# openSX70_ALPHA_V7-20181101.net
KiCad netlist of a schematic drawn in EAGLE
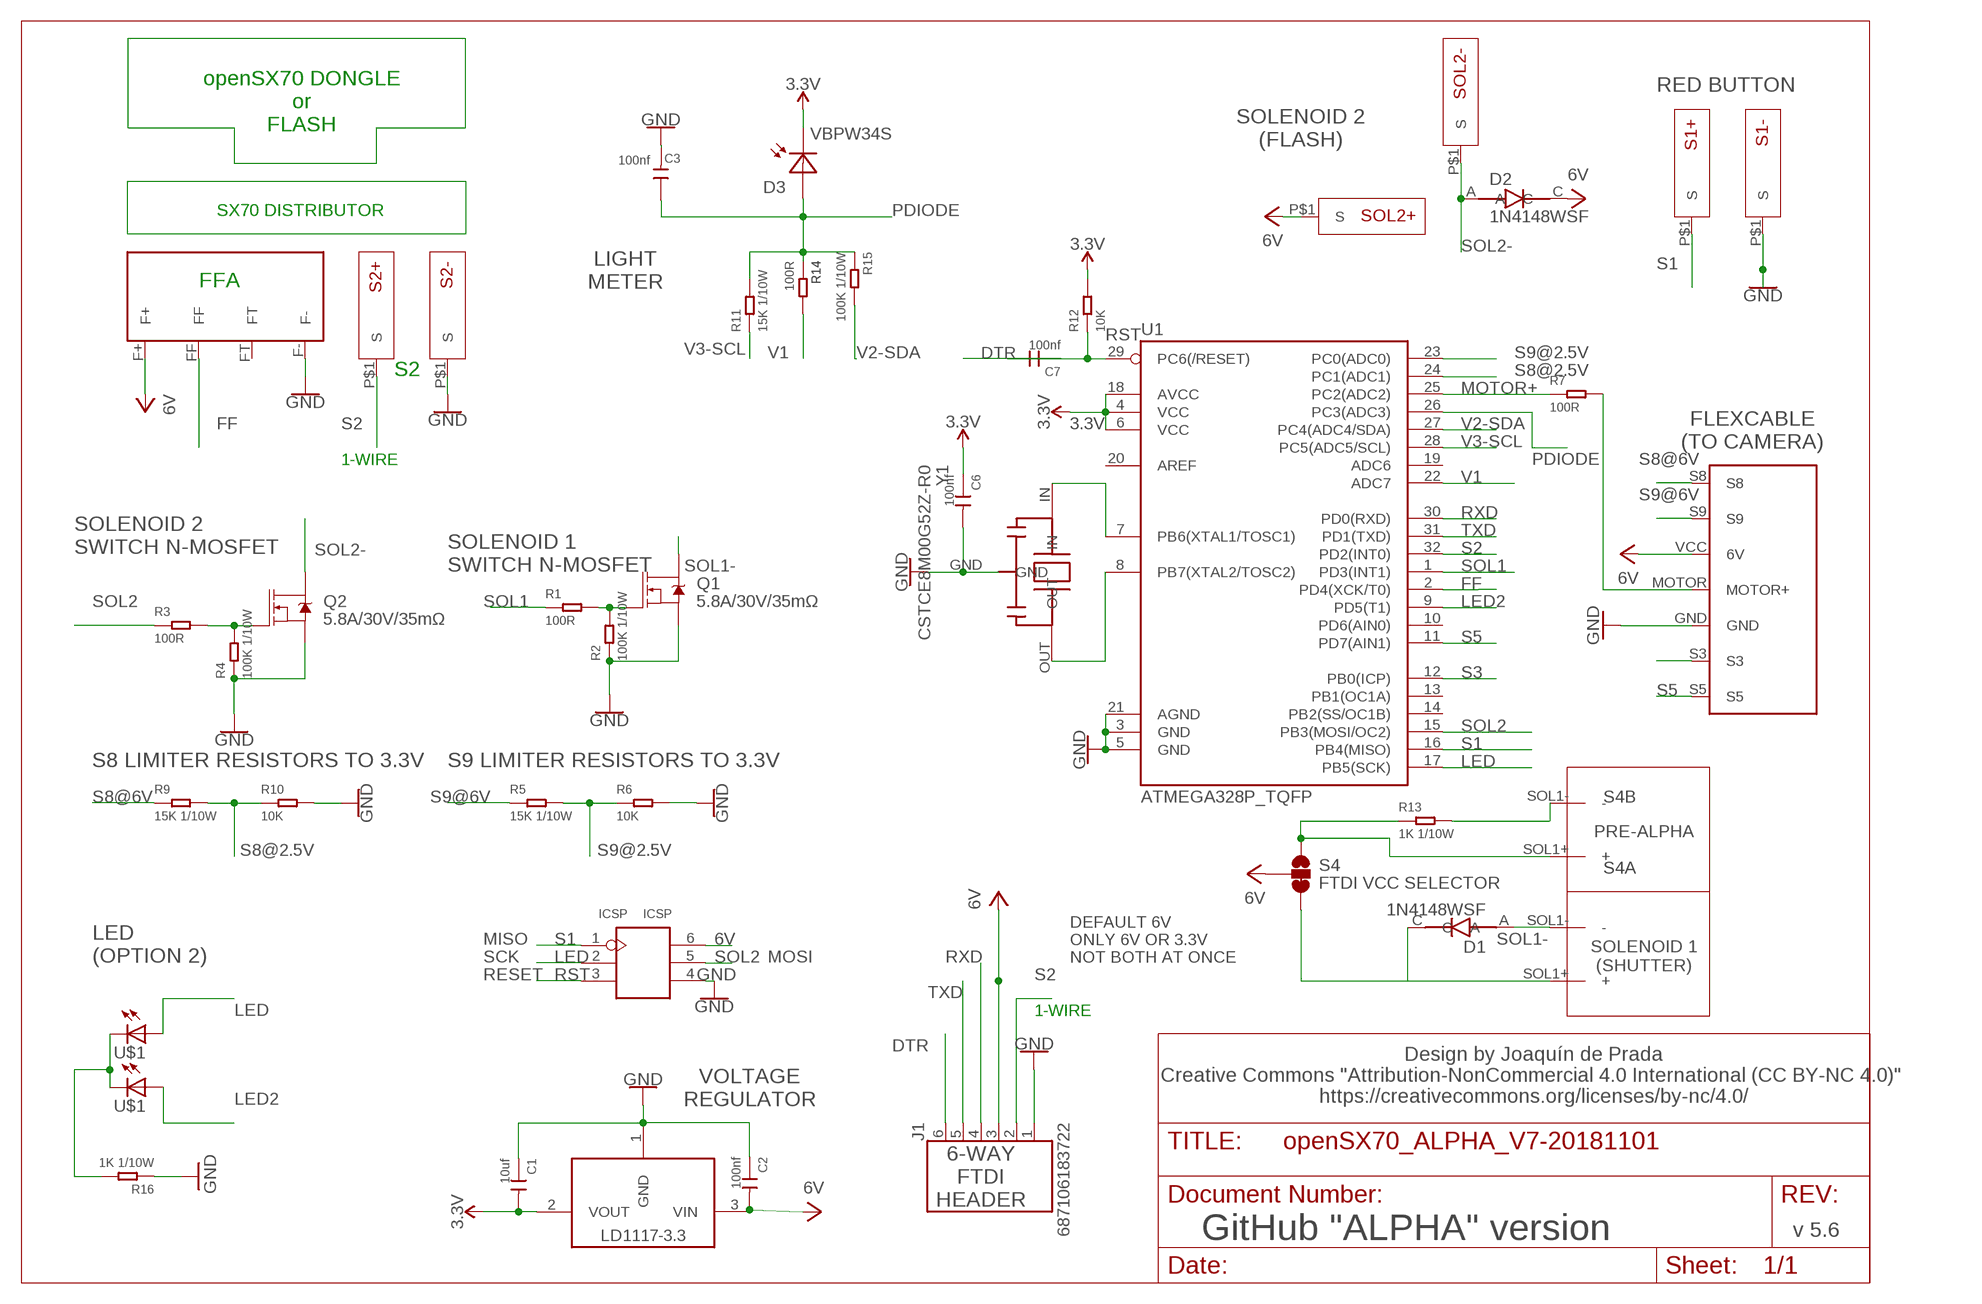
[diagram p0: schematic, sheet 1]

(export (version "E")
  (design (tool "Eeschema 10.0.6"))
  (components
    (comp (ref "C1")
      (value "10uf")
      (footprint "eagle-import:C0603")
      (fields (field (name "MPN") "CC0603KRX5R6BB106"))
      (libsource (lib "eagle-import") (part "CERAMIC-10UF-10V-10%-X5R(0603)"))
    )
    (comp (ref "C2")
      (value "100nf")
      (footprint "eagle-import:C0603")
      (fields (field (name "MPN") "CC0603KRX7R9BB104"))
      (libsource (lib "eagle-import") (part "CERAMIC-100NF-50V-10%-X7R(0603)"))
    )
    (comp (ref "C3")
      (value "100nf")
      (footprint "eagle-import:C0603")
      (fields (field (name "MPN") "CC0603KRX7R9BB104"))
      (libsource (lib "eagle-import") (part "CERAMIC-100NF-50V-10%-X7R(0603)"))
    )
    (comp (ref "C6")
      (value "100nf")
      (footprint "eagle-import:C0603")
      (fields (field (name "MPN") "CC0603KRX7R9BB104"))
      (libsource (lib "eagle-import") (part "CERAMIC-100NF-50V-10%-X7R(0603)"))
    )
    (comp (ref "C7")
      (value "100nf")
      (footprint "eagle-import:C0603")
      (fields (field (name "MPN") "CC0603KRX7R9BB104"))
      (libsource (lib "eagle-import") (part "CERAMIC-100NF-50V-10%-X7R(0603)"))
    )
    (comp (ref "D1")
      (value "1N4148WSF")
      (footprint "eagle-import:SODFL2512X100N")
      (fields (field (name "MANUFACTURER") "Fairchild Semiconductor"))
      (libsource (lib "eagle-import") (part "1N4148WS"))
    )
    (comp (ref "D2")
      (value "1N4148WSF")
      (footprint "eagle-import:SODFL2512X100N")
      (fields (field (name "MANUFACTURER") "Fairchild Semiconductor"))
      (libsource (lib "eagle-import") (part "1N4148WS"))
    )
    (comp (ref "D3")
      (value "VBPW34S")
      (footprint "eagle-import:SOD6439X130N")
      (fields (field (name "DIGI-KEY_PART_NUMBER") "751-1500-1-ND") (field (name "MF") "Vishay"))
      (libsource (lib "eagle-import") (part "VBPW34S"))
    )
    (comp (ref "ICSP")
      (value "ICSP")
      (footprint "eagle-import:H2X3-2.54")
      (libsource (lib "eagle-import") (part "ICSP"))
    )
    (comp (ref "J1")
      (value "687106183722")
      (footprint "eagle-import:687106183722")
      (fields (field (name "MF") "Wurth Electronics"))
      (libsource (lib "eagle-import") (part "687106183722"))
    )
    (comp (ref "LD11172.5V")
      (value "LD1117 2.5V")
      (footprint "eagle-import:SOT223")
      (fields (field (name "MF") "Advanced Monolithic Systems") (field (name "MP") "AMS1117-5.0"))
      (libsource (lib "eagle-import") (part "LD1117-3.3"))
    )
    (comp (ref "Q1")
      (value "5.8A/30V/35mΩ")
      (footprint "eagle-import:SOT23-3")
      (libsource (lib "eagle-import") (part "MOSFET-NCH-AO3404A"))
    )
    (comp (ref "Q2")
      (value "5.8A/30V/35mΩ")
      (footprint "eagle-import:SOT23-3")
      (libsource (lib "eagle-import") (part "MOSFET-NCH-AO3404A"))
    )
    (comp (ref "R1")
      (value "100R")
      (footprint "eagle-import:R0603")
      (fields (field (name "MPN") "RC0603JR-07100RL"))
      (libsource (lib "eagle-import") (part "SMD-RES-100R-5%-1/10W(0603)"))
    )
    (comp (ref "R2")
      (value "100K 1/10W")
      (footprint "eagle-import:R0603")
      (fields (field (name "MPN") "RC0603JR-07100KL"))
      (libsource (lib "eagle-import") (part "SMD-RES-100K-5%-1/10W(0603)"))
    )
    (comp (ref "R3")
      (value "100R")
      (footprint "eagle-import:R0603")
      (fields (field (name "MPN") "RC0603JR-07100RL"))
      (libsource (lib "eagle-import") (part "SMD-RES-100R-5%-1/10W(0603)"))
    )
    (comp (ref "R4")
      (value "100K 1/10W")
      (footprint "eagle-import:R0603")
      (fields (field (name "MPN") "RC0603JR-07100KL"))
      (libsource (lib "eagle-import") (part "SMD-RES-100K-5%-1/10W(0603)"))
    )
    (comp (ref "R5")
      (value "15K 1/10W")
      (footprint "eagle-import:R0603")
      (fields (field (name "MPN") "RC0603FR-0715KL"))
      (libsource (lib "eagle-import") (part "SMD-RES-15K-1%-1/10W(0603)"))
    )
    (comp (ref "R6")
      (value "10K")
      (footprint "eagle-import:R0603")
      (fields (field (name "MPN") "RC0603FR-0710KL"))
      (libsource (lib "eagle-import") (part "SMD-RES-10K-1%-1/10W(0603)"))
    )
    (comp (ref "R7")
      (value "100R")
      (footprint "eagle-import:R0603")
      (fields (field (name "MPN") "RC0603JR-07100RL"))
      (libsource (lib "eagle-import") (part "SMD-RES-100R-5%-1/10W(0603)"))
    )
    (comp (ref "R9")
      (value "15K 1/10W")
      (footprint "eagle-import:R0603")
      (fields (field (name "MPN") "RC0603FR-0715KL"))
      (libsource (lib "eagle-import") (part "SMD-RES-15K-1%-1/10W(0603)"))
    )
    (comp (ref "R10")
      (value "10K")
      (footprint "eagle-import:R0603")
      (fields (field (name "MPN") "RC0603FR-0710KL"))
      (libsource (lib "eagle-import") (part "SMD-RES-10K-1%-1/10W(0603)"))
    )
    (comp (ref "R11")
      (value "15K 1/10W")
      (footprint "eagle-import:R0603")
      (fields (field (name "MPN") "RC0603FR-0715KL"))
      (libsource (lib "eagle-import") (part "SMD-RES-15K-1%-1/10W(0603)"))
    )
    (comp (ref "R12")
      (value "10K")
      (footprint "eagle-import:R0603")
      (fields (field (name "MPN") "RC0603FR-0710KL"))
      (libsource (lib "eagle-import") (part "SMD-RES-10K-1%-1/10W(0603)"))
    )
    (comp (ref "R13")
      (value "1K 1/10W")
      (footprint "eagle-import:R0603")
      (fields (field (name "MPN") "RC0603JR-071KL"))
      (libsource (lib "eagle-import") (part "SMD-RES-1K-5%-1/10W(0603)"))
    )
    (comp (ref "R14")
      (value "100R")
      (footprint "eagle-import:R0603")
      (fields (field (name "MPN") "RC0603JR-07100RL"))
      (libsource (lib "eagle-import") (part "SMD-RES-100R-5%-1/10W(0603)"))
    )
    (comp (ref "R15")
      (value "100K 1/10W")
      (footprint "eagle-import:R0603")
      (fields (field (name "MPN") "RC0603JR-07100KL"))
      (libsource (lib "eagle-import") (part "SMD-RES-100K-5%-1/10W(0603)"))
    )
    (comp (ref "R16")
      (value "1K 1/10W")
      (footprint "eagle-import:R0603")
      (fields (field (name "MPN") "RC0603JR-071KL"))
      (libsource (lib "eagle-import") (part "SMD-RES-1K-5%-1/10W(0603)"))
    )
    (comp (ref "S1+")
      (value "SX70-S-PAD-NEW")
      (footprint "eagle-import:SX70-S-PAD2")
      (libsource (lib "eagle-import") (part "SX70-S-PAD-NEW"))
    )
    (comp (ref "S1-")
      (value "SX70-S-PAD-NEW")
      (footprint "eagle-import:SX70-S-PAD2")
      (libsource (lib "eagle-import") (part "SX70-S-PAD-NEW"))
    )
    (comp (ref "S2+")
      (value "SX70-S-PAD-NEW")
      (footprint "eagle-import:SX70-S-PAD2")
      (libsource (lib "eagle-import") (part "SX70-S-PAD-NEW"))
    )
    (comp (ref "S2-")
      (value "SX70-S-PAD-NEW")
      (footprint "eagle-import:SX70-S-PAD2")
      (libsource (lib "eagle-import") (part "SX70-S-PAD-NEW"))
    )
    (comp (ref "S4")
      (value "FTDI VCC SELECTOR")
      (footprint "eagle-import:SMT-JUMPER_3_1-NC_TRACE_SILK")
      (libsource (lib "eagle-import") (part "JUMPER-SMT_3_1-NC_TRACE_SILK"))
    )
    (comp (ref "SOL1")
      (value "SX70-SOLENOID1-2PADS")
      (footprint "eagle-import:SX70-SOLENOID1-2")
      (libsource (lib "eagle-import") (part "SX70-SOLENOID1-2PADS"))
    )
    (comp (ref "SOL2")
      (value "SX70-SOLENOID1-2PADS")
      (footprint "eagle-import:SX70-SOLENOID1-2")
      (libsource (lib "eagle-import") (part "SX70-SOLENOID1-2PADS"))
    )
    (comp (ref "SOL2+")
      (value "SX70-S-PAD-NEW")
      (footprint "eagle-import:SX70-S-PAD2")
      (libsource (lib "eagle-import") (part "SX70-S-PAD-NEW"))
    )
    (comp (ref "SOL2-")
      (value "SX70-S-PAD-NEW")
      (footprint "eagle-import:SX70-S-PAD2")
      (libsource (lib "eagle-import") (part "SX70-S-PAD-NEW"))
    )
    (comp (ref "U$1")
      (value "DUAL-LED-0603-BIS")
      (footprint "eagle-import:LED_APHB1608SYKSURKC")
      (libsource (lib "eagle-import") (part "DUAL-LED-0603-BIS"))
    )
    (comp (ref "U$2")
      (value "FFA")
      (footprint "eagle-import:FFA-PAD-PACKAGE")
      (libsource (lib "eagle-import") (part "SX70-FFA-PAD"))
    )
    (comp (ref "U$3")
      (value "SX70-7-PAD")
      (footprint "eagle-import:SX70-7-PAD-PROPER")
      (libsource (lib "eagle-import") (part "SX70-7-PAD"))
    )
    (comp (ref "U1")
      (value "ATMEGA328P_TQFP")
      (footprint "eagle-import:TQFP32-08")
      (libsource (lib "eagle-import") (part "ATMEGA328P_TQFP"))
    )
    (comp (ref "Y1")
      (value "CSTCE8M00G52Z-R0")
      (footprint "eagle-import:CFP95P160X100-3N")
      (fields (field (name "MF") "Murata") (field (name "MP") "CSTCE16M0V53-R0"))
      (libsource (lib "eagle-import") (part "CSTCE16M0V53-R0"))
    )
  )
  (nets
    (net (code "1") (name "/DTR") (class "Default")
      (node (ref "C7") (pin "1") (pinfunction "1_1") (pintype "passive"))
      (node (ref "J1") (pin "6") (pinfunction "1_6") (pintype "passive"))
    )
    (net (code "2") (name "/FF") (class "Default")
      (node (ref "U$2") (pin "FF") (pinfunction "FF_FF") (pintype "bidirectional"))
      (node (ref "U1") (pin "2") (pinfunction "PD4(XCK/T0)_2") (pintype "bidirectional"))
    )
    (net (code "3") (name "/LED") (class "Default")
      (node (ref "ICSP") (pin "2") (pinfunction "SCK_2") (pintype "bidirectional"))
      (node (ref "U$1") (pin "1") (pinfunction "A_1") (pintype "passive"))
      (node (ref "U1") (pin "17") (pinfunction "PB5(SCK)_17") (pintype "bidirectional"))
    )
    (net (code "4") (name "/LED2") (class "Default")
      (node (ref "U$1") (pin "3") (pinfunction "A1_3") (pintype "passive"))
      (node (ref "U1") (pin "9") (pinfunction "PD5(T1)_9") (pintype "bidirectional"))
    )
    (net (code "5") (name "/MOTOR+") (class "Default")
      (node (ref "R7") (pin "1") (pinfunction "1_1") (pintype "passive"))
      (node (ref "U1") (pin "25") (pinfunction "PC2(ADC2)_25") (pintype "bidirectional"))
    )
    (net (code "6") (name "/PDIODE") (class "Default")
      (node (ref "C3") (pin "1") (pinfunction "1_1") (pintype "passive"))
      (node (ref "D3") (pin "A") (pinfunction "A_A") (pintype "passive"))
      (node (ref "R11") (pin "2") (pinfunction "2_2") (pintype "passive"))
      (node (ref "R14") (pin "1") (pinfunction "1_1") (pintype "passive"))
      (node (ref "R15") (pin "1") (pinfunction "1_1") (pintype "passive"))
      (node (ref "U1") (pin "26") (pinfunction "PC3(ADC3)_26") (pintype "bidirectional"))
    )
    (net (code "7") (name "/RST") (class "Default")
      (node (ref "C7") (pin "2") (pinfunction "2_2") (pintype "passive"))
      (node (ref "ICSP") (pin "3") (pinfunction "RST_3") (pintype "bidirectional"))
      (node (ref "R12") (pin "1") (pinfunction "1_1") (pintype "passive"))
      (node (ref "U1") (pin "29") (pinfunction "PC6(/RESET)_29") (pintype "bidirectional"))
    )
    (net (code "8") (name "/RXD") (class "Default")
      (node (ref "J1") (pin "4") (pinfunction "3_4") (pintype "passive"))
      (node (ref "U1") (pin "30") (pinfunction "PD0(RXD)_30") (pintype "bidirectional"))
    )
    (net (code "9") (name "/S1") (class "Default")
      (node (ref "ICSP") (pin "1") (pinfunction "MISO_1") (pintype "bidirectional"))
      (node (ref "S1+") (pin "P$1") (pinfunction "S_P$1") (pintype "bidirectional"))
      (node (ref "U1") (pin "16") (pinfunction "PB4(MISO)_16") (pintype "bidirectional"))
    )
    (net (code "10") (name "/S2") (class "Default")
      (node (ref "J1") (pin "2") (pinfunction "5_2") (pintype "passive"))
      (node (ref "S2+") (pin "P$1") (pinfunction "S_P$1") (pintype "bidirectional"))
      (node (ref "U1") (pin "32") (pinfunction "PD2(INT0)_32") (pintype "bidirectional"))
    )
    (net (code "11") (name "/S3") (class "Default")
      (node (ref "U$3") (pin "S3") (pinfunction "S3_S3") (pintype "bidirectional"))
      (node (ref "U1") (pin "12") (pinfunction "PB0(ICP)_12") (pintype "bidirectional"))
    )
    (net (code "12") (name "/S5") (class "Default")
      (node (ref "U$3") (pin "S5") (pinfunction "S5_S5") (pintype "bidirectional"))
      (node (ref "U1") (pin "11") (pinfunction "PD7(AIN1)_11") (pintype "bidirectional"))
    )
    (net (code "13") (name "/S8@2.5V") (class "Default")
      (node (ref "R10") (pin "1") (pinfunction "1_1") (pintype "passive"))
      (node (ref "R9") (pin "2") (pinfunction "2_2") (pintype "passive"))
      (node (ref "U1") (pin "24") (pinfunction "PC1(ADC1)_24") (pintype "bidirectional"))
    )
    (net (code "14") (name "/S8@6V") (class "Default")
      (node (ref "R9") (pin "1") (pinfunction "1_1") (pintype "passive"))
      (node (ref "U$3") (pin "S8") (pinfunction "S8_S8") (pintype "bidirectional"))
    )
    (net (code "15") (name "/S9@2.5V") (class "Default")
      (node (ref "R5") (pin "2") (pinfunction "2_2") (pintype "passive"))
      (node (ref "R6") (pin "1") (pinfunction "1_1") (pintype "passive"))
      (node (ref "U1") (pin "23") (pinfunction "PC0(ADC0)_23") (pintype "bidirectional"))
    )
    (net (code "16") (name "/S9@6V") (class "Default")
      (node (ref "R5") (pin "1") (pinfunction "1_1") (pintype "passive"))
      (node (ref "U$3") (pin "S9") (pinfunction "S9_S9") (pintype "bidirectional"))
    )
    (net (code "17") (name "/SOL1") (class "Default")
      (node (ref "R1") (pin "1") (pinfunction "1_1") (pintype "passive"))
      (node (ref "U1") (pin "1") (pinfunction "PD3(INT1)_1") (pintype "bidirectional"))
    )
    (net (code "18") (name "/SOL1-") (class "Default")
      (node (ref "D1") (pin "A") (pinfunction "A_A") (pintype "passive"))
      (node (ref "Q1") (pin "3") (pinfunction "D_3") (pintype "bidirectional"))
      (node (ref "SOL1") (pin "SOL1-") (pinfunction "-_SOL1-") (pintype "bidirectional"))
    )
    (net (code "19") (name "/SOL2") (class "Default")
      (node (ref "ICSP") (pin "5") (pinfunction "MOSI_5") (pintype "bidirectional"))
      (node (ref "R3") (pin "1") (pinfunction "1_1") (pintype "passive"))
      (node (ref "U1") (pin "15") (pinfunction "PB3(MOSI/OC2)_15") (pintype "bidirectional"))
    )
    (net (code "20") (name "/SOL2-") (class "Default")
      (node (ref "D2") (pin "A") (pinfunction "A_A") (pintype "passive"))
      (node (ref "Q2") (pin "3") (pinfunction "D_3") (pintype "bidirectional"))
      (node (ref "SOL2-") (pin "P$1") (pinfunction "S_P$1") (pintype "bidirectional"))
    )
    (net (code "21") (name "/TXD") (class "Default")
      (node (ref "J1") (pin "5") (pinfunction "2_5") (pintype "passive"))
      (node (ref "U1") (pin "31") (pinfunction "PD1(TXD)_31") (pintype "bidirectional"))
    )
    (net (code "22") (name "/V1") (class "Default")
      (node (ref "R14") (pin "2") (pinfunction "2_2") (pintype "passive"))
      (node (ref "U1") (pin "22") (pinfunction "ADC7_22") (pintype "bidirectional"))
    )
    (net (code "23") (name "/V2-SDA") (class "Default")
      (node (ref "R15") (pin "2") (pinfunction "2_2") (pintype "passive"))
      (node (ref "U1") (pin "27") (pinfunction "PC4(ADC4/SDA)_27") (pintype "bidirectional"))
    )
    (net (code "24") (name "/V3-SCL") (class "Default")
      (node (ref "R11") (pin "1") (pinfunction "1_1") (pintype "passive"))
      (node (ref "U1") (pin "28") (pinfunction "PC5(ADC5/SCL)_28") (pintype "bidirectional"))
    )
    (net (code "25") (name "3.3V") (class "Default")
      (node (ref "C1") (pin "2") (pinfunction "2_2") (pintype "passive"))
      (node (ref "C6") (pin "1") (pinfunction "1_1") (pintype "passive"))
      (node (ref "D3") (pin "C") (pinfunction "C_C") (pintype "passive"))
      (node (ref "LD11172.5V") (pin "2") (pinfunction "VOUT_2") (pintype "bidirectional"))
      (node (ref "R12") (pin "2") (pinfunction "2_2") (pintype "passive"))
      (node (ref "U1") (pin "18") (pinfunction "AVCC_18") (pintype "bidirectional"))
      (node (ref "U1") (pin "4") (pinfunction "VCC_4") (pintype "bidirectional"))
      (node (ref "U1") (pin "6") (pinfunction "VCC_6") (pintype "bidirectional"))
    )
    (net (code "26") (name "6V") (class "Default")
      (node (ref "C2") (pin "2") (pinfunction "2_2") (pintype "passive"))
      (node (ref "D2") (pin "C") (pinfunction "C_C") (pintype "passive"))
      (node (ref "ICSP") (pin "6") (pinfunction "VCC_6") (pintype "bidirectional"))
      (node (ref "J1") (pin "3") (pinfunction "4_3") (pintype "passive"))
      (node (ref "LD11172.5V") (pin "3") (pinfunction "VIN_3") (pintype "bidirectional"))
      (node (ref "S4") (pin "2") (pinfunction "2_2") (pintype "passive"))
      (node (ref "SOL2+") (pin "P$1") (pinfunction "S_P$1") (pintype "bidirectional"))
      (node (ref "U$2") (pin "F+") (pinfunction "F+_F+") (pintype "bidirectional"))
      (node (ref "U$3") (pin "VCC") (pinfunction "6V_VCC") (pintype "bidirectional"))
    )
    (net (code "27") (name "GND") (class "Default")
      (node (ref "C1") (pin "1") (pinfunction "1_1") (pintype "passive"))
      (node (ref "C2") (pin "1") (pinfunction "1_1") (pintype "passive"))
      (node (ref "C3") (pin "2") (pinfunction "2_2") (pintype "passive"))
      (node (ref "C6") (pin "2") (pinfunction "2_2") (pintype "passive"))
      (node (ref "ICSP") (pin "4") (pinfunction "GND_4") (pintype "bidirectional"))
      (node (ref "J1") (pin "1") (pinfunction "6_1") (pintype "passive"))
      (node (ref "LD11172.5V") (pin "1") (pinfunction "GND_1") (pintype "bidirectional"))
      (node (ref "Q1") (pin "2") (pinfunction "S_2") (pintype "bidirectional"))
      (node (ref "Q2") (pin "2") (pinfunction "S_2") (pintype "bidirectional"))
      (node (ref "R10") (pin "2") (pinfunction "2_2") (pintype "passive"))
      (node (ref "R16") (pin "1") (pinfunction "1_1") (pintype "passive"))
      (node (ref "R2") (pin "1") (pinfunction "1_1") (pintype "passive"))
      (node (ref "R4") (pin "1") (pinfunction "1_1") (pintype "passive"))
      (node (ref "R6") (pin "2") (pinfunction "2_2") (pintype "passive"))
      (node (ref "S1-") (pin "P$1") (pinfunction "S_P$1") (pintype "bidirectional"))
      (node (ref "S2-") (pin "P$1") (pinfunction "S_P$1") (pintype "bidirectional"))
      (node (ref "U$2") (pin "F-") (pinfunction "F-_F-") (pintype "bidirectional"))
      (node (ref "U$3") (pin "GND") (pinfunction "GND_GND") (pintype "bidirectional"))
      (node (ref "U1") (pin "21") (pinfunction "AGND_21") (pintype "bidirectional"))
      (node (ref "U1") (pin "3") (pinfunction "GND_3") (pintype "bidirectional"))
      (node (ref "U1") (pin "5") (pinfunction "GND_5") (pintype "bidirectional"))
      (node (ref "Y1") (pin "GND") (pinfunction "GND_GND") (pintype "passive"))
    )
    (net (code "28") (name "Net-(Q1-G)") (class "Default")
      (node (ref "Q1") (pin "1") (pinfunction "G_1") (pintype "bidirectional"))
      (node (ref "R1") (pin "2") (pinfunction "2_2") (pintype "passive"))
      (node (ref "R2") (pin "2") (pinfunction "2_2") (pintype "passive"))
    )
    (net (code "29") (name "Net-(Q2-G)") (class "Default")
      (node (ref "Q2") (pin "1") (pinfunction "G_1") (pintype "bidirectional"))
      (node (ref "R3") (pin "2") (pinfunction "2_2") (pintype "passive"))
      (node (ref "R4") (pin "2") (pinfunction "2_2") (pintype "passive"))
    )
    (net (code "30") (name "Net-(SOL1-+)") (class "Default")
      (node (ref "D1") (pin "C") (pinfunction "C_C") (pintype "passive"))
      (node (ref "S4") (pin "3") (pinfunction "3_3") (pintype "passive"))
      (node (ref "SOL1") (pin "SOL1+") (pinfunction "+_SOL1+") (pintype "bidirectional"))
    )
    (net (code "31") (name "Net-(SOL2-+)") (class "Default")
      (node (ref "R13") (pin "1") (pinfunction "1_1") (pintype "passive"))
      (node (ref "S4") (pin "1") (pinfunction "1_1") (pintype "passive"))
      (node (ref "SOL2") (pin "SOL1+") (pinfunction "+_SOL1+") (pintype "bidirectional"))
    )
    (net (code "32") (name "Net-(SOL2--)") (class "Default")
      (node (ref "R13") (pin "2") (pinfunction "2_2") (pintype "passive"))
      (node (ref "SOL2") (pin "SOL1-") (pinfunction "-_SOL1-") (pintype "bidirectional"))
    )
    (net (code "33") (name "Net-(U$1-C)") (class "Default")
      (node (ref "R16") (pin "2") (pinfunction "2_2") (pintype "passive"))
      (node (ref "U$1") (pin "2") (pinfunction "C_2") (pintype "passive"))
      (node (ref "U$1") (pin "4") (pinfunction "C1_4") (pintype "passive"))
    )
    (net (code "34") (name "Net-(U$3-MOTOR+)") (class "Default")
      (node (ref "R7") (pin "2") (pinfunction "2_2") (pintype "passive"))
      (node (ref "U$3") (pin "MOTOR") (pinfunction "MOTOR+_MOTOR") (pintype "bidirectional"))
    )
    (net (code "35") (name "Net-(U1-PB6(XTAL1{slash}TOSC1))") (class "Default")
      (node (ref "U1") (pin "7") (pinfunction "PB6(XTAL1/TOSC1)_7") (pintype "bidirectional"))
      (node (ref "Y1") (pin "IN") (pinfunction "IN_IN") (pintype "input"))
    )
    (net (code "36") (name "Net-(U1-PB7(XTAL2{slash}TOSC2))") (class "Default")
      (node (ref "U1") (pin "8") (pinfunction "PB7(XTAL2/TOSC2)_8") (pintype "bidirectional"))
      (node (ref "Y1") (pin "OUT") (pinfunction "OUT_OUT") (pintype "output"))
    )
    (net (code "37") (name "unconnected-(U$2-PadFT)") (class "Default")
      (node (ref "U$2") (pin "FT") (pinfunction "FT_FT") (pintype "bidirectional"))
    )
    (net (code "38") (name "unconnected-(U1-ADC6-Pad19)") (class "Default")
      (node (ref "U1") (pin "19") (pinfunction "ADC6_19") (pintype "bidirectional"))
    )
    (net (code "39") (name "unconnected-(U1-AREF-Pad20)") (class "Default")
      (node (ref "U1") (pin "20") (pinfunction "AREF_20") (pintype "bidirectional"))
    )
    (net (code "40") (name "unconnected-(U1-PB1(OC1A)-Pad13)") (class "Default")
      (node (ref "U1") (pin "13") (pinfunction "PB1(OC1A)_13") (pintype "bidirectional"))
    )
    (net (code "41") (name "unconnected-(U1-PB2(SS{slash}OC1B)-Pad14)") (class "Default")
      (node (ref "U1") (pin "14") (pinfunction "PB2(SS/OC1B)_14") (pintype "bidirectional"))
    )
    (net (code "42") (name "unconnected-(U1-PD6(AIN0)-Pad10)") (class "Default")
      (node (ref "U1") (pin "10") (pinfunction "PD6(AIN0)_10") (pintype "bidirectional"))
    )
  )
)
